# dtb220-schematic.net
KiCad netlist of a schematic drawn in Altium Designer
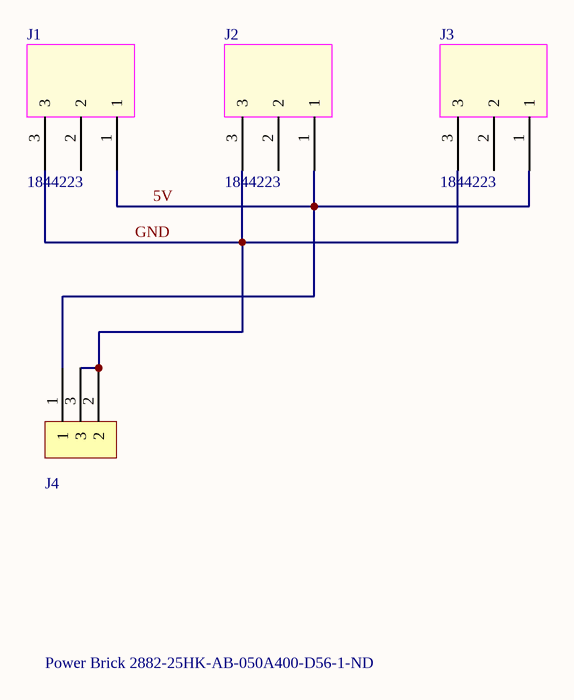
[diagram p0: dtb220-schematic.SchDoc]

(export (version "E")
  (design (tool "Eeschema 10.0.6"))
  (components
    (comp (ref "J1")
      (value "1844223")
      (footprint "1844223")
      (fields (field (name "MANUFACTURER") "Phoenix Contact"))
      (libsource (lib "Allen_Integrated_Library") (part "1844223"))
    )
    (comp (ref "J2")
      (value "1844223")
      (footprint "1844223")
      (fields (field (name "MANUFACTURER") "Phoenix Contact"))
      (libsource (lib "Allen_Integrated_Library") (part "1844223"))
    )
    (comp (ref "J3")
      (value "1844223")
      (footprint "1844223")
      (fields (field (name "MANUFACTURER") "Phoenix Contact"))
      (libsource (lib "Allen_Integrated_Library") (part "1844223"))
    )
    (comp (ref "J4")
      (value "EJ508A")
      (footprint "EJ508A")
      (description "CONN PWR JACK 2.1X5.5MM SOLDER")
      (fields (field (name "MANUFACTURER") "MPD"))
      (libsource (lib "emma-altium-lib") (part "EJ508A"))
    )
  )
  (nets
    (net (code "1") (name "/5V") (class "Default")
      (node (ref "J1") (pin "1") (pinfunction "1_1") (pintype "passive"))
      (node (ref "J2") (pin "1") (pinfunction "1_1") (pintype "passive"))
      (node (ref "J3") (pin "1") (pinfunction "1_1") (pintype "passive"))
      (node (ref "J4") (pin "1") (pinfunction "1_1") (pintype "passive"))
    )
    (net (code "2") (name "/GND") (class "Default")
      (node (ref "J1") (pin "3") (pinfunction "3_3") (pintype "passive"))
      (node (ref "J2") (pin "3") (pinfunction "3_3") (pintype "passive"))
      (node (ref "J3") (pin "3") (pinfunction "3_3") (pintype "passive"))
      (node (ref "J4") (pin "2") (pinfunction "2_2") (pintype "passive"))
      (node (ref "J4") (pin "3") (pinfunction "3_3") (pintype "passive"))
    )
    (net (code "3") (name "unconnected-(J1-Pad2)") (class "Default")
      (node (ref "J1") (pin "2") (pinfunction "2_2") (pintype "passive"))
    )
    (net (code "4") (name "unconnected-(J2-Pad2)") (class "Default")
      (node (ref "J2") (pin "2") (pinfunction "2_2") (pintype "passive"))
    )
    (net (code "5") (name "unconnected-(J3-Pad2)") (class "Default")
      (node (ref "J3") (pin "2") (pinfunction "2_2") (pintype "passive"))
    )
  )
)
